# USBboard.net
KiCad netlist of a schematic drawn in EAGLE
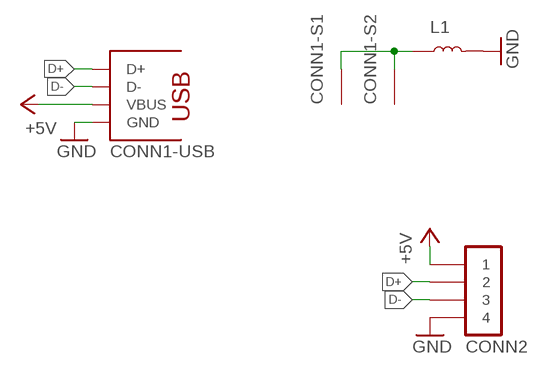
[diagram p0: schematic, sheet 1]

(export (version "E")
  (design (tool "Eeschema 10.0.6"))
  (components
    (comp (ref "CONN1")
      (value "USB-B-V")
      (footprint "eagle-import:USB-B-PTH-V")
      (fields (field (name "MANUFACTURER") "CUI Devices") (field (name "MPN") "UJ2-BV-1-TH"))
      (libsource (lib "eagle-import") (part "USB-B-V"))
    )
    (comp (ref "CONN2")
      (value "PINHD-1X04-JST-XH-H")
      (footprint "eagle-import:JST-XH-04P-H")
      (libsource (lib "eagle-import") (part "PINHD-1X04-JST-XH-H"))
    )
    (comp (ref "L1")
      (value "FERRITE_BEAD-BLM21PG221SN1D")
      (footprint "eagle-import:L0805")
      (fields (field (name "MANUFACTURER") "Murata") (field (name "MPN") "BLM21PG221SN1D"))
      (libsource (lib "eagle-import") (part "FERRITE_BEAD-BLM21PG221SN1D"))
    )
  )
  (nets
    (net (code "1") (name "+5V") (class "Default")
      (node (ref "CONN1") (pin "VBUS") (pinfunction "VBUS_VBUS") (pintype "bidirectional"))
      (node (ref "CONN2") (pin "1") (pinfunction "1_1") (pintype "passive"))
    )
    (net (code "2") (name "D+") (class "Default")
      (node (ref "CONN1") (pin "D+") (pinfunction "D+_D+") (pintype "bidirectional"))
      (node (ref "CONN2") (pin "2") (pinfunction "2_2") (pintype "passive"))
    )
    (net (code "3") (name "D-") (class "Default")
      (node (ref "CONN1") (pin "D-") (pinfunction "D-_D-") (pintype "bidirectional"))
      (node (ref "CONN2") (pin "3") (pinfunction "3_3") (pintype "passive"))
    )
    (net (code "4") (name "GND") (class "Default")
      (node (ref "CONN1") (pin "GND") (pinfunction "GND_GND") (pintype "bidirectional"))
      (node (ref "CONN2") (pin "4") (pinfunction "4_4") (pintype "passive"))
      (node (ref "L1") (pin "2") (pinfunction "2_2") (pintype "passive"))
    )
    (net (code "5") (name "Net-(CONN1A-S)") (class "Default")
      (node (ref "CONN1") (pin "S1") (pinfunction "S_S1") (pintype "passive"))
      (node (ref "CONN1") (pin "S2") (pinfunction "S_S2") (pintype "passive"))
      (node (ref "L1") (pin "1") (pinfunction "1_1") (pintype "passive"))
    )
  )
)
